# Select_Measure.net
KiCad netlist of a schematic drawn in Altium Designer
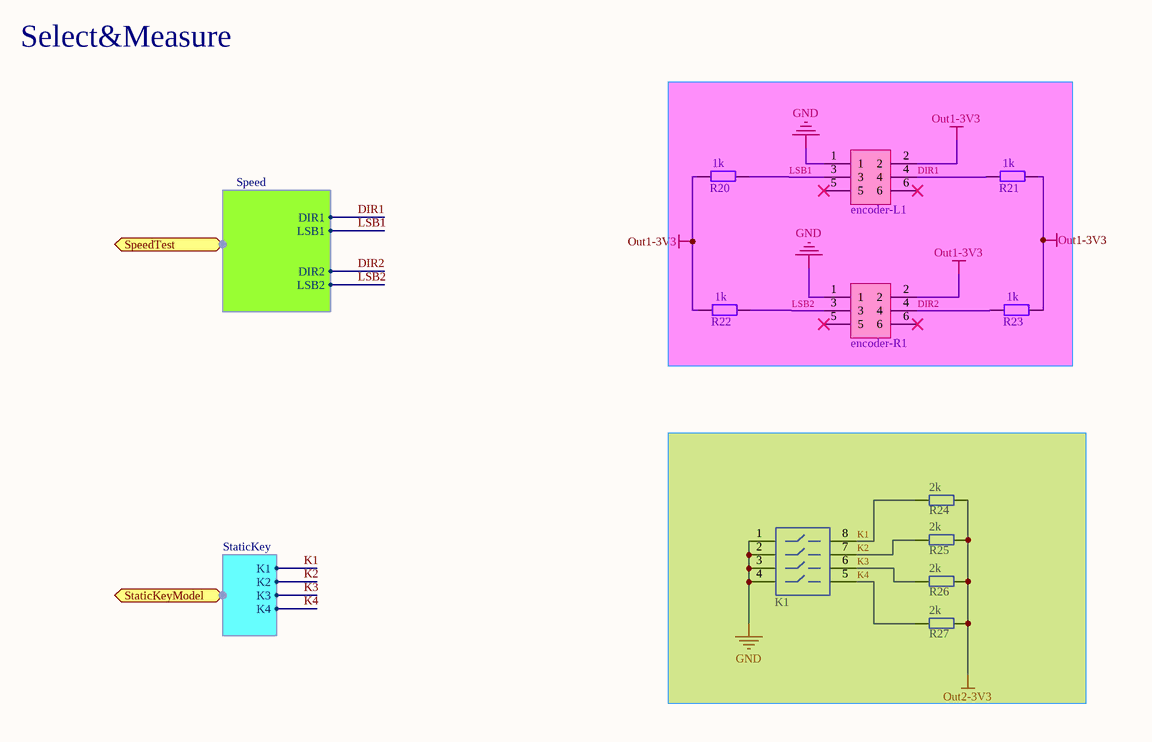
[diagram p0: Select&Measure.SchDoc]

(export (version "E")
  (design (tool "Eeschema 10.0.6"))
  (components
    (comp (ref "encoder-L1") (value "编码器") (footprint "编码器") (libsource (lib "常用原件库") (part "编码器")))
    (comp (ref "encoder-R1") (value "编码器") (footprint "编码器") (libsource (lib "常用原件库") (part "编码器")))
    (comp (ref "K1") (value "拨码开关") (footprint "拨码开关") (libsource (lib "常用原件库") (part "拨码开关")))
    (comp (ref "R20") (value "1k") (footprint "0805电阻") (libsource (lib "常用原件库") (part "0805电阻")))
    (comp (ref "R21") (value "1k") (footprint "0805电阻") (libsource (lib "常用原件库") (part "0805电阻")))
    (comp (ref "R22") (value "1k") (footprint "0805电阻") (libsource (lib "常用原件库") (part "0805电阻")))
    (comp (ref "R23") (value "1k") (footprint "0805电阻") (libsource (lib "常用原件库") (part "0805电阻")))
    (comp (ref "R24") (value "2k") (footprint "0805电阻") (libsource (lib "常用原件库") (part "0805电阻")))
    (comp (ref "R25") (value "2k") (footprint "0805电阻") (libsource (lib "常用原件库") (part "0805电阻")))
    (comp (ref "R26") (value "2k") (footprint "0805电阻") (libsource (lib "常用原件库") (part "0805电阻")))
    (comp (ref "R27") (value "2k") (footprint "0805电阻") (libsource (lib "常用原件库") (part "0805电阻")))
  )
  (nets
    (net (code "3") (name "/DIR1") (class "Default")
      (node (ref "R21") (pin "1") (pinfunction "1_1") (pintype "passive"))
      (node (ref "encoder-L1") (pin "4") (pinfunction "4_4") (pintype "passive"))
    )
    (net (code "4") (name "/DIR2") (class "Default")
      (node (ref "R23") (pin "1") (pinfunction "1_1") (pintype "passive"))
      (node (ref "encoder-R1") (pin "4") (pinfunction "4_4") (pintype "passive"))
    )
    (net (code "5") (name "/K1") (class "Default")
      (node (ref "K1") (pin "8") (pinfunction "8_8") (pintype "passive"))
      (node (ref "R24") (pin "1") (pinfunction "1_1") (pintype "passive"))
    )
    (net (code "6") (name "/K2") (class "Default")
      (node (ref "K1") (pin "7") (pinfunction "7_7") (pintype "passive"))
      (node (ref "R25") (pin "1") (pinfunction "1_1") (pintype "passive"))
    )
    (net (code "7") (name "/K3") (class "Default")
      (node (ref "K1") (pin "6") (pinfunction "6_6") (pintype "passive"))
      (node (ref "R26") (pin "1") (pinfunction "1_1") (pintype "passive"))
    )
    (net (code "8") (name "/K4") (class "Default")
      (node (ref "K1") (pin "5") (pinfunction "5_5") (pintype "passive"))
      (node (ref "R27") (pin "1") (pinfunction "1_1") (pintype "passive"))
    )
    (net (code "9") (name "/LSB1") (class "Default")
      (node (ref "R20") (pin "2") (pinfunction "2_2") (pintype "passive"))
      (node (ref "encoder-L1") (pin "3") (pinfunction "3_3") (pintype "passive"))
    )
    (net (code "10") (name "/LSB2") (class "Default")
      (node (ref "R22") (pin "2") (pinfunction "2_2") (pintype "passive"))
      (node (ref "encoder-R1") (pin "3") (pinfunction "3_3") (pintype "passive"))
    )
    (net (code "13") (name "GND") (class "Default")
      (node (ref "K1") (pin "1") (pinfunction "1_1") (pintype "passive"))
      (node (ref "K1") (pin "2") (pinfunction "2_2") (pintype "passive"))
      (node (ref "K1") (pin "3") (pinfunction "3_3") (pintype "passive"))
      (node (ref "K1") (pin "4") (pinfunction "4_4") (pintype "passive"))
      (node (ref "encoder-L1") (pin "1") (pinfunction "1_1") (pintype "passive"))
      (node (ref "encoder-R1") (pin "1") (pinfunction "1_1") (pintype "passive"))
    )
    (net (code "14") (name "Out1-3V3") (class "Default")
      (node (ref "R20") (pin "1") (pinfunction "1_1") (pintype "passive"))
      (node (ref "R21") (pin "2") (pinfunction "2_2") (pintype "passive"))
      (node (ref "R22") (pin "1") (pinfunction "1_1") (pintype "passive"))
      (node (ref "R23") (pin "2") (pinfunction "2_2") (pintype "passive"))
      (node (ref "encoder-L1") (pin "2") (pinfunction "2_2") (pintype "passive"))
      (node (ref "encoder-R1") (pin "2") (pinfunction "2_2") (pintype "passive"))
    )
    (net (code "15") (name "Out2-3V3") (class "Default")
      (node (ref "R24") (pin "2") (pinfunction "2_2") (pintype "passive"))
      (node (ref "R25") (pin "2") (pinfunction "2_2") (pintype "passive"))
      (node (ref "R26") (pin "2") (pinfunction "2_2") (pintype "passive"))
      (node (ref "R27") (pin "2") (pinfunction "2_2") (pintype "passive"))
    )
    (net (code "16") (name "unconnected-(encoder-L1-Pad5)") (class "Default")
      (node (ref "encoder-L1") (pin "5") (pinfunction "5_5") (pintype "passive+no_connect"))
    )
    (net (code "17") (name "unconnected-(encoder-L1-Pad6)") (class "Default")
      (node (ref "encoder-L1") (pin "6") (pinfunction "6_6") (pintype "passive+no_connect"))
    )
    (net (code "18") (name "unconnected-(encoder-R1-Pad5)") (class "Default")
      (node (ref "encoder-R1") (pin "5") (pinfunction "5_5") (pintype "passive+no_connect"))
    )
    (net (code "19") (name "unconnected-(encoder-R1-Pad6)") (class "Default")
      (node (ref "encoder-R1") (pin "6") (pinfunction "6_6") (pintype "passive+no_connect"))
    )
  )
)
